# USB_ETH_Mux.net
KiCad netlist of a schematic drawn in Altium Designer
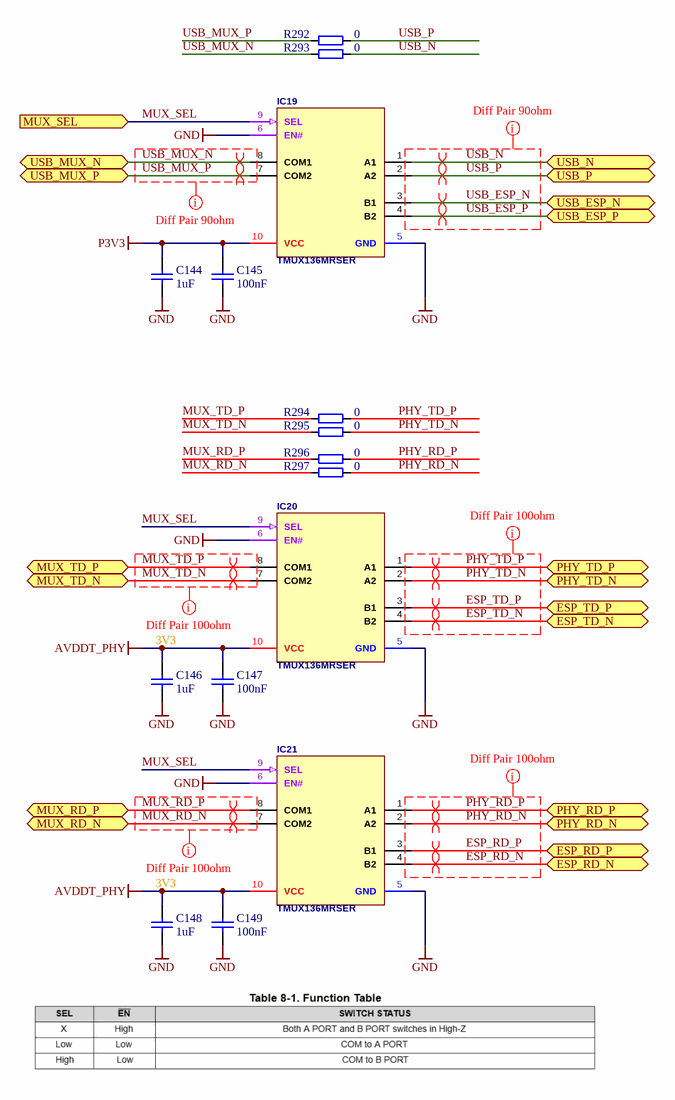
[diagram p0: USB_ETH_Mux.SchDoc]

(export (version "E")
  (design (tool "Eeschema 10.0.6"))
  (components
    (comp (ref "C144")
      (value "1uF")
      (footprint "CAPC1005X55N")
      (description "Non-polarised capacitor")
      (fields
        (field (name "PART NUMBER") "CC0402_1UF_16V_10%_X5R")
        (field (name "VOLTAGE") "16V")
        (field (name "AUTHOR") "CERN DEM JLC")
      )
      (libsource (lib "Capacitors") (part "Capacitor - non polarized"))
    )
    (comp (ref "C145")
      (value "100nF")
      (footprint "CAPC1005X55N")
      (description "Non-polarised capacitor")
      (fields
        (field (name "PART NUMBER") "CC0402_100NF_16V_10%_X5R")
        (field (name "VOLTAGE") "16V")
        (field (name "AUTHOR") "CERN DEM JLC")
      )
      (libsource (lib "Capacitors") (part "Capacitor - non polarized"))
    )
    (comp (ref "C146")
      (value "1uF")
      (footprint "CAPC1005X55N")
      (description "Non-polarised capacitor")
      (fields
        (field (name "PART NUMBER") "CC0402_1UF_16V_10%_X5R")
        (field (name "VOLTAGE") "16V")
        (field (name "AUTHOR") "CERN DEM JLC")
      )
      (libsource (lib "Capacitors") (part "Capacitor - non polarized"))
    )
    (comp (ref "C147")
      (value "100nF")
      (footprint "CAPC1005X55N")
      (description "Non-polarised capacitor")
      (fields
        (field (name "PART NUMBER") "CC0402_100NF_16V_10%_X5R")
        (field (name "VOLTAGE") "16V")
        (field (name "AUTHOR") "CERN DEM JLC")
      )
      (libsource (lib "Capacitors") (part "Capacitor - non polarized"))
    )
    (comp (ref "C148")
      (value "1uF")
      (footprint "CAPC1005X55N")
      (description "Non-polarised capacitor")
      (fields
        (field (name "PART NUMBER") "CC0402_1UF_16V_10%_X5R")
        (field (name "VOLTAGE") "16V")
        (field (name "AUTHOR") "CERN DEM JLC")
      )
      (libsource (lib "Capacitors") (part "Capacitor - non polarized"))
    )
    (comp (ref "C149")
      (value "100nF")
      (footprint "CAPC1005X55N")
      (description "Non-polarised capacitor")
      (fields
        (field (name "PART NUMBER") "CC0402_100NF_16V_10%_X5R")
        (field (name "VOLTAGE") "16V")
        (field (name "AUTHOR") "CERN DEM JLC")
      )
      (libsource (lib "Capacitors") (part "Capacitor - non polarized"))
    )
    (comp (ref "IC19")
      (value "TMUX136MRSER")
      (footprint "TI_RSE0010A")
      (description "Two-Channel Differential 2:1 MUX or 1:2 Demux")
      (fields (field (name "MANUFACTURER") "Texas Instruments"))
      (libsource (lib "STM_System_Board") (part "TMUX136"))
    )
    (comp (ref "IC20")
      (value "TMUX136MRSER")
      (footprint "TI_RSE0010A")
      (description "Two-Channel Differential 2:1 MUX or 1:2 Demux")
      (fields (field (name "MANUFACTURER") "Texas Instruments"))
      (libsource (lib "STM_System_Board") (part "TMUX136"))
    )
    (comp (ref "IC21")
      (value "TMUX136MRSER")
      (footprint "TI_RSE0010A")
      (description "Two-Channel Differential 2:1 MUX or 1:2 Demux")
      (fields (field (name "MANUFACTURER") "Texas Instruments"))
      (libsource (lib "STM_System_Board") (part "TMUX136"))
    )
    (comp (ref "R292")
      (value "0")
      (footprint "RESC1005X40N")
      (description "Resistor")
      (fields
        (field (name "PART NUMBER") "R0402_0R_JUMPER")
        (field (name "MANUFACTURER") "GENERIC")
        (field (name "AUTHOR") "CERN DEM JLC")
      )
      (libsource (lib "Resistors") (part "Resistor"))
    )
    (comp (ref "R293")
      (value "0")
      (footprint "RESC1005X40N")
      (description "Resistor")
      (fields
        (field (name "PART NUMBER") "R0402_0R_JUMPER")
        (field (name "MANUFACTURER") "GENERIC")
        (field (name "AUTHOR") "CERN DEM JLC")
      )
      (libsource (lib "Resistors") (part "Resistor"))
    )
    (comp (ref "R294")
      (value "0")
      (footprint "RESC1005X40N")
      (description "Resistor")
      (fields
        (field (name "PART NUMBER") "R0402_0R_JUMPER")
        (field (name "MANUFACTURER") "GENERIC")
        (field (name "AUTHOR") "CERN DEM JLC")
      )
      (libsource (lib "Resistors") (part "Resistor"))
    )
    (comp (ref "R295")
      (value "0")
      (footprint "RESC1005X40N")
      (description "Resistor")
      (fields
        (field (name "PART NUMBER") "R0402_0R_JUMPER")
        (field (name "MANUFACTURER") "GENERIC")
        (field (name "AUTHOR") "CERN DEM JLC")
      )
      (libsource (lib "Resistors") (part "Resistor"))
    )
    (comp (ref "R296")
      (value "0")
      (footprint "RESC1005X40N")
      (description "Resistor")
      (fields
        (field (name "PART NUMBER") "R0402_0R_JUMPER")
        (field (name "MANUFACTURER") "GENERIC")
        (field (name "AUTHOR") "CERN DEM JLC")
      )
      (libsource (lib "Resistors") (part "Resistor"))
    )
    (comp (ref "R297")
      (value "0")
      (footprint "RESC1005X40N")
      (description "Resistor")
      (fields
        (field (name "PART NUMBER") "R0402_0R_JUMPER")
        (field (name "MANUFACTURER") "GENERIC")
        (field (name "AUTHOR") "CERN DEM JLC")
      )
      (libsource (lib "Resistors") (part "Resistor"))
    )
  )
  (nets
    (net (code "1") (name "/ESP_RD_N") (class "Default")
      (node (ref "IC21") (pin "4") (pinfunction "B2_4") (pintype "passive"))
    )
    (net (code "2") (name "/ESP_RD_P") (class "Default")
      (node (ref "IC21") (pin "3") (pinfunction "B1_3") (pintype "passive"))
    )
    (net (code "3") (name "/ESP_TD_N") (class "Default")
      (node (ref "IC20") (pin "4") (pinfunction "B2_4") (pintype "passive"))
    )
    (net (code "4") (name "/ESP_TD_P") (class "Default")
      (node (ref "IC20") (pin "3") (pinfunction "B1_3") (pintype "passive"))
    )
    (net (code "5") (name "/MUX_RD_N") (class "Default")
      (node (ref "IC21") (pin "7") (pinfunction "COM2_7") (pintype "passive"))
      (node (ref "R297") (pin "1") (pinfunction "1_1") (pintype "passive"))
    )
    (net (code "6") (name "/MUX_RD_P") (class "Default")
      (node (ref "IC21") (pin "8") (pinfunction "COM1_8") (pintype "passive"))
      (node (ref "R296") (pin "1") (pinfunction "1_1") (pintype "passive"))
    )
    (net (code "7") (name "/MUX_SEL") (class "Default")
      (node (ref "IC19") (pin "9") (pinfunction "SEL_9") (pintype "input"))
      (node (ref "IC20") (pin "9") (pinfunction "SEL_9") (pintype "input"))
      (node (ref "IC21") (pin "9") (pinfunction "SEL_9") (pintype "input"))
    )
    (net (code "8") (name "/MUX_TD_N") (class "Default")
      (node (ref "IC20") (pin "7") (pinfunction "COM2_7") (pintype "passive"))
      (node (ref "R295") (pin "1") (pinfunction "1_1") (pintype "passive"))
    )
    (net (code "9") (name "/MUX_TD_P") (class "Default")
      (node (ref "IC20") (pin "8") (pinfunction "COM1_8") (pintype "passive"))
      (node (ref "R294") (pin "1") (pinfunction "1_1") (pintype "passive"))
    )
    (net (code "10") (name "/PHY_RD_N") (class "Default")
      (node (ref "IC21") (pin "2") (pinfunction "A2_2") (pintype "passive"))
      (node (ref "R297") (pin "2") (pinfunction "2_2") (pintype "passive"))
    )
    (net (code "11") (name "/PHY_RD_P") (class "Default")
      (node (ref "IC21") (pin "1") (pinfunction "A1_1") (pintype "passive"))
      (node (ref "R296") (pin "2") (pinfunction "2_2") (pintype "passive"))
    )
    (net (code "12") (name "/PHY_TD_N") (class "Default")
      (node (ref "IC20") (pin "2") (pinfunction "A2_2") (pintype "passive"))
      (node (ref "R295") (pin "2") (pinfunction "2_2") (pintype "passive"))
    )
    (net (code "13") (name "/PHY_TD_P") (class "Default")
      (node (ref "IC20") (pin "1") (pinfunction "A1_1") (pintype "passive"))
      (node (ref "R294") (pin "2") (pinfunction "2_2") (pintype "passive"))
    )
    (net (code "14") (name "/USB_ESP_N") (class "Default")
      (node (ref "IC19") (pin "3") (pinfunction "B1_3") (pintype "passive"))
    )
    (net (code "15") (name "/USB_ESP_P") (class "Default")
      (node (ref "IC19") (pin "4") (pinfunction "B2_4") (pintype "passive"))
    )
    (net (code "16") (name "/USB_MUX_N") (class "Default")
      (node (ref "IC19") (pin "8") (pinfunction "COM1_8") (pintype "passive"))
      (node (ref "R293") (pin "1") (pinfunction "1_1") (pintype "passive"))
    )
    (net (code "17") (name "/USB_MUX_P") (class "Default")
      (node (ref "IC19") (pin "7") (pinfunction "COM2_7") (pintype "passive"))
      (node (ref "R292") (pin "1") (pinfunction "1_1") (pintype "passive"))
    )
    (net (code "18") (name "/USB_N") (class "Default")
      (node (ref "IC19") (pin "1") (pinfunction "A1_1") (pintype "passive"))
      (node (ref "R293") (pin "2") (pinfunction "2_2") (pintype "passive"))
    )
    (net (code "19") (name "/USB_P") (class "Default")
      (node (ref "IC19") (pin "2") (pinfunction "A2_2") (pintype "passive"))
      (node (ref "R292") (pin "2") (pinfunction "2_2") (pintype "passive"))
    )
    (net (code "20") (name "AVDDT_PHY") (class "Default")
      (node (ref "C146") (pin "2") (pinfunction "2_2") (pintype "passive"))
      (node (ref "C147") (pin "1") (pinfunction "1_1") (pintype "passive"))
      (node (ref "C148") (pin "2") (pinfunction "2_2") (pintype "passive"))
      (node (ref "C149") (pin "1") (pinfunction "1_1") (pintype "passive"))
      (node (ref "IC20") (pin "10") (pinfunction "VCC_10") (pintype "passive"))
      (node (ref "IC21") (pin "10") (pinfunction "VCC_10") (pintype "passive"))
    )
    (net (code "21") (name "GND") (class "Default")
      (node (ref "C144") (pin "1") (pinfunction "1_1") (pintype "passive"))
      (node (ref "C145") (pin "2") (pinfunction "2_2") (pintype "passive"))
      (node (ref "C146") (pin "1") (pinfunction "1_1") (pintype "passive"))
      (node (ref "C147") (pin "2") (pinfunction "2_2") (pintype "passive"))
      (node (ref "C148") (pin "1") (pinfunction "1_1") (pintype "passive"))
      (node (ref "C149") (pin "2") (pinfunction "2_2") (pintype "passive"))
      (node (ref "IC19") (pin "5") (pinfunction "GND_5") (pintype "passive"))
      (node (ref "IC19") (pin "6") (pinfunction "EN#_6") (pintype "passive"))
      (node (ref "IC20") (pin "5") (pinfunction "GND_5") (pintype "passive"))
      (node (ref "IC20") (pin "6") (pinfunction "EN#_6") (pintype "passive"))
      (node (ref "IC21") (pin "5") (pinfunction "GND_5") (pintype "passive"))
      (node (ref "IC21") (pin "6") (pinfunction "EN#_6") (pintype "passive"))
    )
    (net (code "22") (name "P3V3") (class "Default")
      (node (ref "C144") (pin "2") (pinfunction "2_2") (pintype "passive"))
      (node (ref "C145") (pin "1") (pinfunction "1_1") (pintype "passive"))
      (node (ref "IC19") (pin "10") (pinfunction "VCC_10") (pintype "passive"))
    )
  )
)
